# sx-wdec-smd-4313.net
KiCad netlist of a schematic drawn in EAGLE
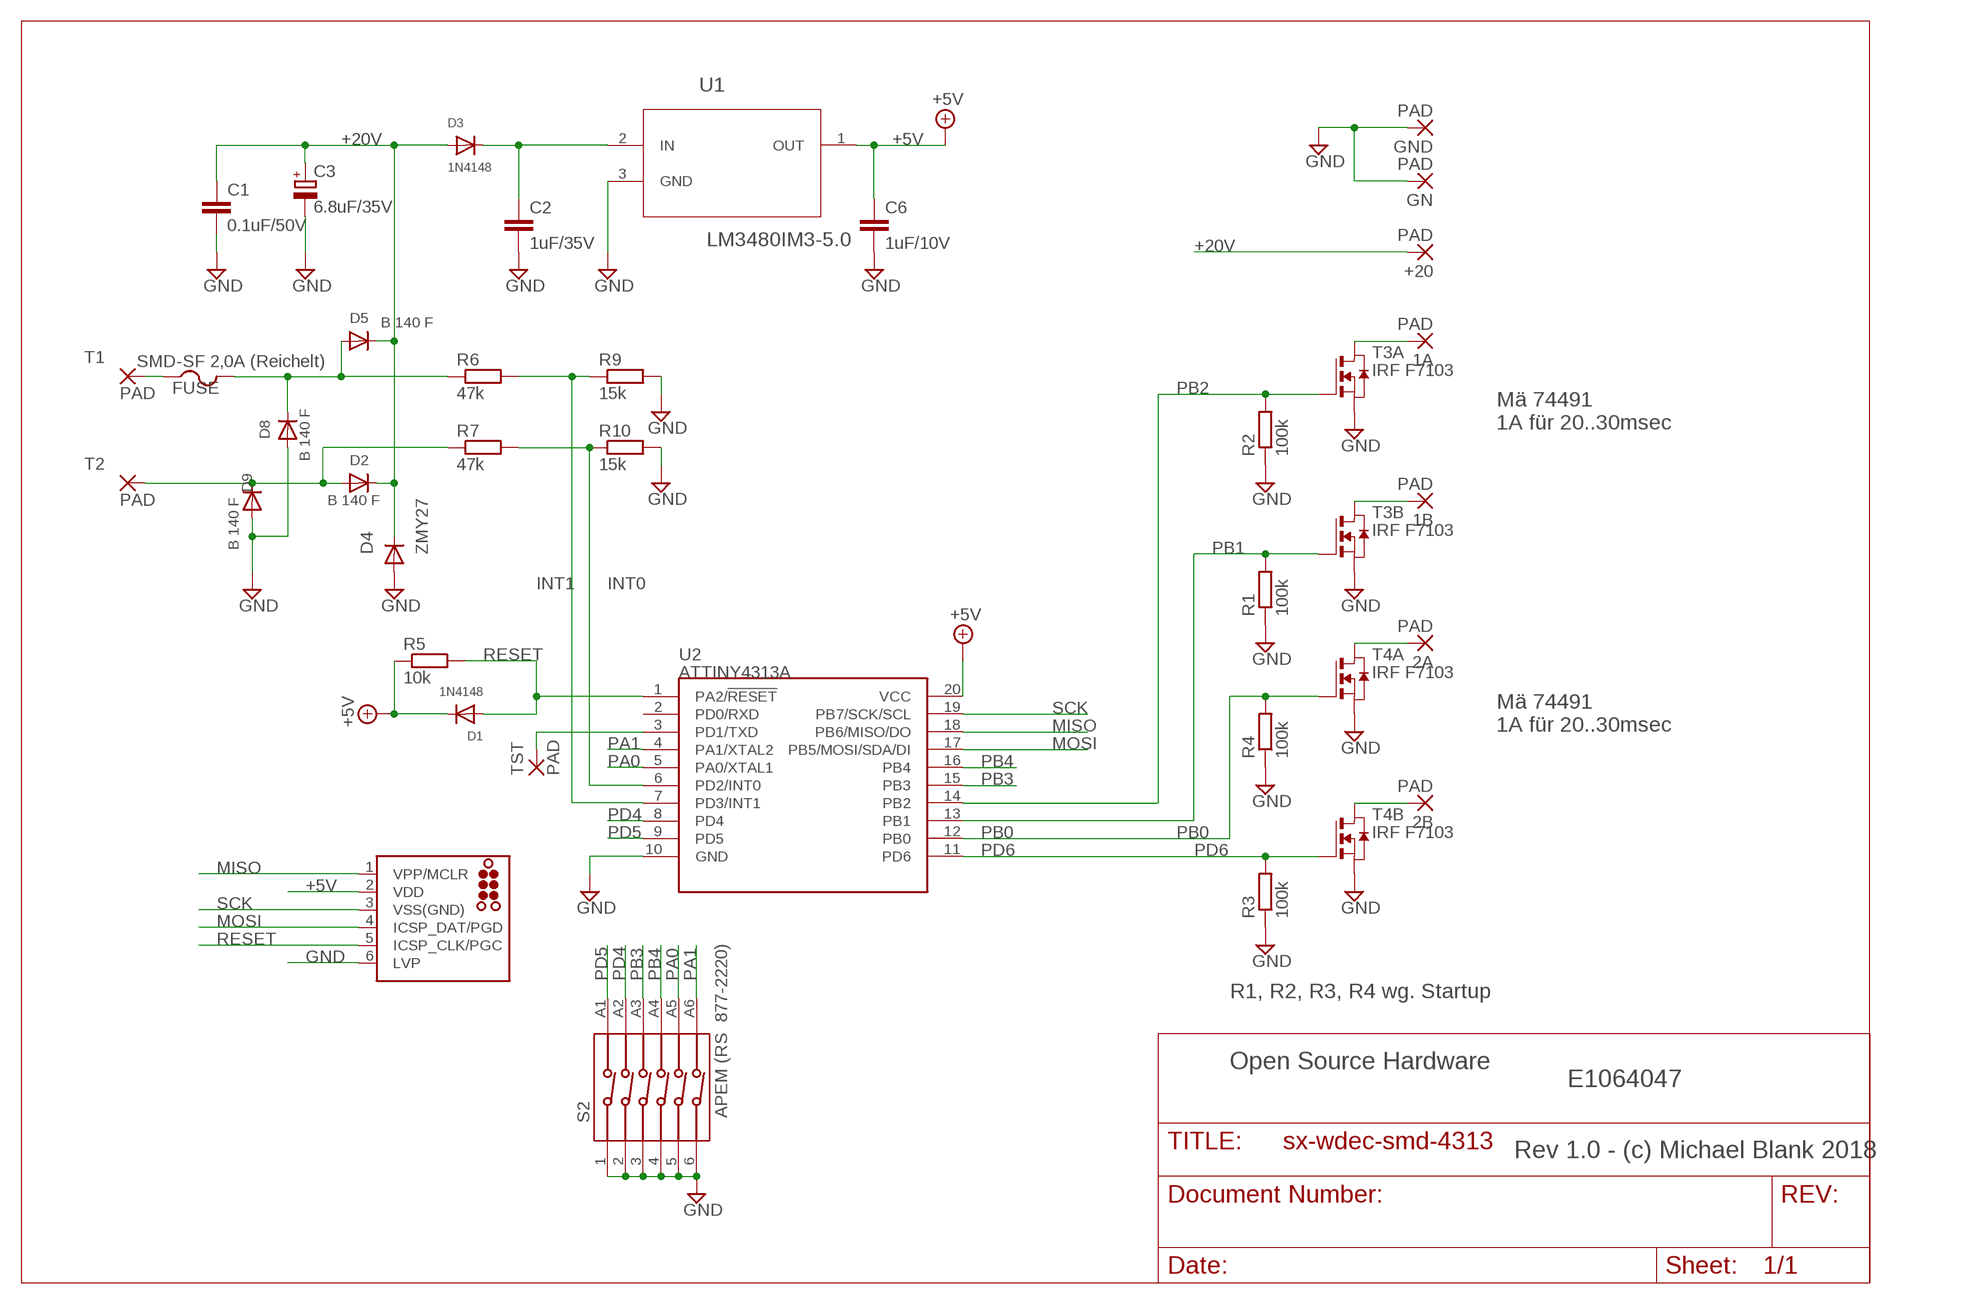
[diagram p0: schematic, sheet 1]

(export (version "E")
  (design (tool "Eeschema 10.0.6"))
  (components
    (comp (ref "+20")
      (value "PAD")
      (footprint "eagle-import:SMD1,27-2,54")
      (libsource (lib "eagle-import") (part "SMD2"))
    )
    (comp (ref "1A")
      (value "PAD")
      (footprint "eagle-import:SMD1,27-2,54")
      (libsource (lib "eagle-import") (part "SMD2"))
    )
    (comp (ref "1B")
      (value "PAD")
      (footprint "eagle-import:SMD1,27-2,54")
      (libsource (lib "eagle-import") (part "SMD2"))
    )
    (comp (ref "2A")
      (value "PAD")
      (footprint "eagle-import:SMD1,27-2,54")
      (libsource (lib "eagle-import") (part "SMD2"))
    )
    (comp (ref "2B")
      (value "PAD")
      (footprint "eagle-import:SMD1,27-2,54")
      (libsource (lib "eagle-import") (part "SMD2"))
    )
    (comp (ref "C1")
      (value "0.1uF/50V")
      (footprint "eagle-import:C0805")
      (libsource (lib "eagle-import") (part "C-EUC0805"))
    )
    (comp (ref "C2")
      (value "1uF/35V")
      (footprint "eagle-import:C0805")
      (libsource (lib "eagle-import") (part "C-EUC0805"))
    )
    (comp (ref "C3")
      (value "6.8uF/35V")
      (footprint "eagle-import:SMC_D")
      (libsource (lib "eagle-import") (part "CPOL-EUSMCD"))
    )
    (comp (ref "C6")
      (value "1uF/10V")
      (footprint "eagle-import:C0805")
      (libsource (lib "eagle-import") (part "C-EUC0805"))
    )
    (comp (ref "D1")
      (value "1N4148")
      (footprint "eagle-import:SOD-323F")
      (libsource (lib "eagle-import") (part "DIODESOD-323F"))
    )
    (comp (ref "D2")
      (value "B 140 F")
      (footprint "eagle-import:SMA-403D")
      (libsource (lib "eagle-import") (part "DIODESMA-403D"))
    )
    (comp (ref "D3")
      (value "1N4148")
      (footprint "eagle-import:SOD-323F")
      (libsource (lib "eagle-import") (part "DIODESOD-323F"))
    )
    (comp (ref "D4")
      (value "ZMY27")
      (footprint "eagle-import:MELF-MLL41")
      (libsource (lib "eagle-import") (part "DIODE-MELF-MLL41"))
    )
    (comp (ref "D5")
      (value "B 140 F")
      (footprint "eagle-import:SMA-403D")
      (libsource (lib "eagle-import") (part "DIODESMA-403D"))
    )
    (comp (ref "D8")
      (value "B 140 F")
      (footprint "eagle-import:SMA-403D")
      (libsource (lib "eagle-import") (part "DIODESMA-403D"))
    )
    (comp (ref "D9")
      (value "B 140 F")
      (footprint "eagle-import:SMA-403D")
      (libsource (lib "eagle-import") (part "DIODESMA-403D"))
    )
    (comp (ref "FUSE")
      (value "SMD-SF 2,0A (Reichelt)")
      (footprint "eagle-import:1812")
      (libsource (lib "eagle-import") (part "PTCFUSE-1812"))
    )
    (comp (ref "GN")
      (value "PAD")
      (footprint "eagle-import:SMD1,27-2,54")
      (libsource (lib "eagle-import") (part "SMD2"))
    )
    (comp (ref "GND")
      (value "PAD")
      (footprint "eagle-import:SMD1,27-2,54")
      (libsource (lib "eagle-import") (part "SMD2"))
    )
    (comp (ref "J1")
      (value "ISP")
      (footprint "eagle-import:TC2030-MCP-NL")
      (libsource (lib "eagle-import") (part "TC2030-MCP-NL"))
    )
    (comp (ref "R1")
      (value "100k")
      (footprint "eagle-import:R0805W")
      (libsource (lib "eagle-import") (part "R-EU_R0805W"))
    )
    (comp (ref "R2")
      (value "100k")
      (footprint "eagle-import:R0805W")
      (libsource (lib "eagle-import") (part "R-EU_R0805W"))
    )
    (comp (ref "R3")
      (value "100k")
      (footprint "eagle-import:R0805W")
      (libsource (lib "eagle-import") (part "R-EU_R0805W"))
    )
    (comp (ref "R4")
      (value "100k")
      (footprint "eagle-import:R0805W")
      (libsource (lib "eagle-import") (part "R-EU_R0805W"))
    )
    (comp (ref "R5")
      (value "10k")
      (footprint "eagle-import:R0805W")
      (libsource (lib "eagle-import") (part "R-EU_R0805W"))
    )
    (comp (ref "R6")
      (value "47k")
      (footprint "eagle-import:R0805W")
      (libsource (lib "eagle-import") (part "R-EU_R0805W"))
    )
    (comp (ref "R7")
      (value "47k")
      (footprint "eagle-import:R0805W")
      (libsource (lib "eagle-import") (part "R-EU_R0805W"))
    )
    (comp (ref "R9")
      (value "15k")
      (footprint "eagle-import:R0805W")
      (libsource (lib "eagle-import") (part "R-EU_R0805W"))
    )
    (comp (ref "R10")
      (value "15k")
      (footprint "eagle-import:R0805W")
      (libsource (lib "eagle-import") (part "R-EU_R0805W"))
    )
    (comp (ref "S2")
      (value "APEM (RS 877-2220)")
      (footprint "eagle-import:416131160806")
      (libsource (lib "eagle-import") (part "416131160806"))
    )
    (comp (ref "T1")
      (value "PAD")
      (footprint "eagle-import:SMD1,27-2,54")
      (libsource (lib "eagle-import") (part "SMD2"))
    )
    (comp (ref "T2")
      (value "PAD")
      (footprint "eagle-import:SMD1,27-2,54")
      (libsource (lib "eagle-import") (part "SMD2"))
    )
    (comp (ref "T3")
      (value "IRF F7103")
      (footprint "eagle-import:SO8")
      (libsource (lib "eagle-import") (part "DMN3024LSD"))
    )
    (comp (ref "T4")
      (value "IRF F7103")
      (footprint "eagle-import:SO8")
      (libsource (lib "eagle-import") (part "DMN3024LSD"))
    )
    (comp (ref "TST")
      (value "PAD")
      (footprint "eagle-import:SMD1,27-2,54")
      (libsource (lib "eagle-import") (part "SMD2"))
    )
    (comp (ref "U1")
      (value "LM3480IM3-5.0")
      (footprint "eagle-import:SOT95P263X110-3N")
      (fields (field (name "MPN") "LM3480IM3-50"))
      (libsource (lib "eagle-import") (part "LM3480IM3-5.0"))
    )
    (comp (ref "U2")
      (value "ATTINY4313A")
      (footprint "eagle-import:SOP20W")
      (libsource (lib "eagle-import") (part "ATTINY2313A"))
    )
  )
  (nets
    (net (code "1") (name "+5V") (class "Default")
      (node (ref "C6") (pin "1") (pinfunction "1_1") (pintype "passive"))
      (node (ref "D1") (pin "C") (pinfunction "C_C") (pintype "passive"))
      (node (ref "J1") (pin "2") (pinfunction "VDD_2") (pintype "power_in"))
      (node (ref "R5") (pin "1") (pinfunction "1_1") (pintype "passive"))
      (node (ref "U1") (pin "1") (pinfunction "OUT_1") (pintype "output"))
      (node (ref "U2") (pin "20") (pinfunction "VCC_20") (pintype "bidirectional"))
    )
    (net (code "2") (name "/+20V") (class "Default")
      (node (ref "+20") (pin "1") (pinfunction "P_1") (pintype "passive"))
      (node (ref "C1") (pin "1") (pinfunction "1_1") (pintype "passive"))
      (node (ref "C3") (pin "+") (pinfunction "+_+") (pintype "passive"))
      (node (ref "D2") (pin "C") (pinfunction "C_C") (pintype "passive"))
      (node (ref "D3") (pin "A") (pinfunction "A_A") (pintype "passive"))
      (node (ref "D4") (pin "C") (pinfunction "C_C") (pintype "passive"))
      (node (ref "D5") (pin "C") (pinfunction "C_C") (pintype "passive"))
    )
    (net (code "3") (name "/INT0") (class "Default")
      (node (ref "R10") (pin "1") (pinfunction "1_1") (pintype "passive"))
      (node (ref "R7") (pin "2") (pinfunction "2_2") (pintype "passive"))
      (node (ref "U2") (pin "6") (pinfunction "PD2/INT0_6") (pintype "bidirectional"))
    )
    (net (code "4") (name "/INT1") (class "Default")
      (node (ref "R6") (pin "2") (pinfunction "2_2") (pintype "passive"))
      (node (ref "R9") (pin "1") (pinfunction "1_1") (pintype "passive"))
      (node (ref "U2") (pin "7") (pinfunction "PD3/INT1_7") (pintype "bidirectional"))
    )
    (net (code "5") (name "/MISO") (class "Default")
      (node (ref "J1") (pin "1") (pinfunction "VPP/MCLR_1") (pintype "passive"))
      (node (ref "U2") (pin "18") (pinfunction "PB6/MISO/DO_18") (pintype "bidirectional"))
    )
    (net (code "6") (name "/MOSI") (class "Default")
      (node (ref "J1") (pin "4") (pinfunction "ICSP_DAT/PGD_4") (pintype "bidirectional"))
      (node (ref "U2") (pin "17") (pinfunction "PB5/MOSI/SDA/DI_17") (pintype "bidirectional"))
    )
    (net (code "7") (name "/PA0") (class "Default")
      (node (ref "S2") (pin "A5") (pinfunction "A5_A5") (pintype "passive"))
      (node (ref "U2") (pin "5") (pinfunction "PA0/XTAL1_5") (pintype "bidirectional"))
    )
    (net (code "8") (name "/PA1") (class "Default")
      (node (ref "S2") (pin "A6") (pinfunction "A6_A6") (pintype "passive"))
      (node (ref "U2") (pin "4") (pinfunction "PA1/XTAL2_4") (pintype "bidirectional"))
    )
    (net (code "9") (name "/PB0") (class "Default")
      (node (ref "R4") (pin "2") (pinfunction "2_2") (pintype "passive"))
      (node (ref "T4") (pin "2") (pinfunction "G_2") (pintype "passive"))
      (node (ref "U2") (pin "12") (pinfunction "PB0_12") (pintype "bidirectional"))
    )
    (net (code "10") (name "/PB1") (class "Default")
      (node (ref "R1") (pin "2") (pinfunction "2_2") (pintype "passive"))
      (node (ref "T3") (pin "4") (pinfunction "G_4") (pintype "passive"))
      (node (ref "U2") (pin "13") (pinfunction "PB1_13") (pintype "bidirectional"))
    )
    (net (code "11") (name "/PB2") (class "Default")
      (node (ref "R2") (pin "2") (pinfunction "2_2") (pintype "passive"))
      (node (ref "T3") (pin "2") (pinfunction "G_2") (pintype "passive"))
      (node (ref "U2") (pin "14") (pinfunction "PB2_14") (pintype "bidirectional"))
    )
    (net (code "12") (name "/PB3") (class "Default")
      (node (ref "S2") (pin "A3") (pinfunction "A3_A3") (pintype "passive"))
      (node (ref "U2") (pin "15") (pinfunction "PB3_15") (pintype "bidirectional"))
    )
    (net (code "13") (name "/PB4") (class "Default")
      (node (ref "S2") (pin "A4") (pinfunction "A4_A4") (pintype "passive"))
      (node (ref "U2") (pin "16") (pinfunction "PB4_16") (pintype "bidirectional"))
    )
    (net (code "14") (name "/PD4") (class "Default")
      (node (ref "S2") (pin "A2") (pinfunction "A2_A2") (pintype "passive"))
      (node (ref "U2") (pin "8") (pinfunction "PD4_8") (pintype "bidirectional"))
    )
    (net (code "15") (name "/PD5") (class "Default")
      (node (ref "S2") (pin "A1") (pinfunction "A1_A1") (pintype "passive"))
      (node (ref "U2") (pin "9") (pinfunction "PD5_9") (pintype "bidirectional"))
    )
    (net (code "16") (name "/PD6") (class "Default")
      (node (ref "R3") (pin "2") (pinfunction "2_2") (pintype "passive"))
      (node (ref "T4") (pin "4") (pinfunction "G_4") (pintype "passive"))
      (node (ref "U2") (pin "11") (pinfunction "PD6_11") (pintype "bidirectional"))
    )
    (net (code "17") (name "/RESET") (class "Default")
      (node (ref "D1") (pin "A") (pinfunction "A_A") (pintype "passive"))
      (node (ref "J1") (pin "5") (pinfunction "ICSP_CLK/PGC_5") (pintype "output"))
      (node (ref "R5") (pin "2") (pinfunction "2_2") (pintype "passive"))
      (node (ref "U2") (pin "1") (pinfunction "PA2/~{RESET}_1") (pintype "bidirectional"))
    )
    (net (code "18") (name "/SCK") (class "Default")
      (node (ref "J1") (pin "3") (pinfunction "VSS(GND)_3") (pintype "power_in"))
      (node (ref "U2") (pin "19") (pinfunction "PB7/SCK/SCL_19") (pintype "bidirectional"))
    )
    (net (code "19") (name "GND") (class "Default")
      (node (ref "C1") (pin "2") (pinfunction "2_2") (pintype "passive"))
      (node (ref "C2") (pin "2") (pinfunction "2_2") (pintype "passive"))
      (node (ref "C3") (pin "-") (pinfunction "-_-") (pintype "passive"))
      (node (ref "C6") (pin "2") (pinfunction "2_2") (pintype "passive"))
      (node (ref "D4") (pin "A") (pinfunction "A_A") (pintype "passive"))
      (node (ref "D8") (pin "A") (pinfunction "A_A") (pintype "passive"))
      (node (ref "D9") (pin "A") (pinfunction "A_A") (pintype "passive"))
      (node (ref "GN") (pin "1") (pinfunction "P_1") (pintype "passive"))
      (node (ref "GND") (pin "1") (pinfunction "P_1") (pintype "passive"))
      (node (ref "J1") (pin "6") (pinfunction "LVP_6") (pintype "bidirectional"))
      (node (ref "R1") (pin "1") (pinfunction "1_1") (pintype "passive"))
      (node (ref "R10") (pin "2") (pinfunction "2_2") (pintype "passive"))
      (node (ref "R2") (pin "1") (pinfunction "1_1") (pintype "passive"))
      (node (ref "R3") (pin "1") (pinfunction "1_1") (pintype "passive"))
      (node (ref "R4") (pin "1") (pinfunction "1_1") (pintype "passive"))
      (node (ref "R9") (pin "2") (pinfunction "2_2") (pintype "passive"))
      (node (ref "S2") (pin "1") (pinfunction "1_1") (pintype "passive"))
      (node (ref "S2") (pin "2") (pinfunction "2_2") (pintype "passive"))
      (node (ref "S2") (pin "3") (pinfunction "3_3") (pintype "passive"))
      (node (ref "S2") (pin "4") (pinfunction "4_4") (pintype "passive"))
      (node (ref "S2") (pin "5") (pinfunction "5_5") (pintype "passive"))
      (node (ref "S2") (pin "6") (pinfunction "6_6") (pintype "passive"))
      (node (ref "T3") (pin "1") (pinfunction "S_1") (pintype "passive"))
      (node (ref "T3") (pin "3") (pinfunction "S_3") (pintype "passive"))
      (node (ref "T4") (pin "1") (pinfunction "S_1") (pintype "passive"))
      (node (ref "T4") (pin "3") (pinfunction "S_3") (pintype "passive"))
      (node (ref "U1") (pin "3") (pinfunction "GND_3") (pintype "passive"))
      (node (ref "U2") (pin "10") (pinfunction "GND_10") (pintype "bidirectional"))
    )
    (net (code "20") (name "Net-(1A-P)") (class "Default")
      (node (ref "1A") (pin "1") (pinfunction "P_1") (pintype "passive"))
      (node (ref "T3") (pin "7") (pinfunction "D_7") (pintype "passive"))
      (node (ref "T3") (pin "8") (pinfunction "D_8") (pintype "passive"))
    )
    (net (code "21") (name "Net-(1B-P)") (class "Default")
      (node (ref "1B") (pin "1") (pinfunction "P_1") (pintype "passive"))
      (node (ref "T3") (pin "5") (pinfunction "D_5") (pintype "passive"))
      (node (ref "T3") (pin "6") (pinfunction "D_6") (pintype "passive"))
    )
    (net (code "22") (name "Net-(2A-P)") (class "Default")
      (node (ref "2A") (pin "1") (pinfunction "P_1") (pintype "passive"))
      (node (ref "T4") (pin "7") (pinfunction "D_7") (pintype "passive"))
      (node (ref "T4") (pin "8") (pinfunction "D_8") (pintype "passive"))
    )
    (net (code "23") (name "Net-(2B-P)") (class "Default")
      (node (ref "2B") (pin "1") (pinfunction "P_1") (pintype "passive"))
      (node (ref "T4") (pin "5") (pinfunction "D_5") (pintype "passive"))
      (node (ref "T4") (pin "6") (pinfunction "D_6") (pintype "passive"))
    )
    (net (code "24") (name "Net-(D5-PadA)") (class "Default")
      (node (ref "D5") (pin "A") (pinfunction "A_A") (pintype "passive"))
      (node (ref "D8") (pin "C") (pinfunction "C_C") (pintype "passive"))
      (node (ref "FUSE") (pin "2") (pinfunction "2_2") (pintype "passive"))
      (node (ref "R6") (pin "1") (pinfunction "1_1") (pintype "passive"))
    )
    (net (code "25") (name "Net-(T1-P)") (class "Default")
      (node (ref "FUSE") (pin "1") (pinfunction "1_1") (pintype "passive"))
      (node (ref "T1") (pin "1") (pinfunction "P_1") (pintype "passive"))
    )
    (net (code "26") (name "Net-(T2-P)") (class "Default")
      (node (ref "D2") (pin "A") (pinfunction "A_A") (pintype "passive"))
      (node (ref "D9") (pin "C") (pinfunction "C_C") (pintype "passive"))
      (node (ref "R7") (pin "1") (pinfunction "1_1") (pintype "passive"))
      (node (ref "T2") (pin "1") (pinfunction "P_1") (pintype "passive"))
    )
    (net (code "27") (name "Net-(TST-P)") (class "Default")
      (node (ref "TST") (pin "1") (pinfunction "P_1") (pintype "passive"))
      (node (ref "U2") (pin "3") (pinfunction "PD1/TXD_3") (pintype "bidirectional"))
    )
    (net (code "28") (name "Net-(U1-IN)") (class "Default")
      (node (ref "C2") (pin "1") (pinfunction "1_1") (pintype "passive"))
      (node (ref "D3") (pin "C") (pinfunction "C_C") (pintype "passive"))
      (node (ref "U1") (pin "2") (pinfunction "IN_2") (pintype "power_in"))
    )
    (net (code "29") (name "unconnected-(U2-PD0{slash}RXD-Pad2)") (class "Default")
      (node (ref "U2") (pin "2") (pinfunction "PD0/RXD_2") (pintype "bidirectional"))
    )
  )
)
